# iot_env_mote.net
KiCad netlist of a schematic drawn in EAGLE
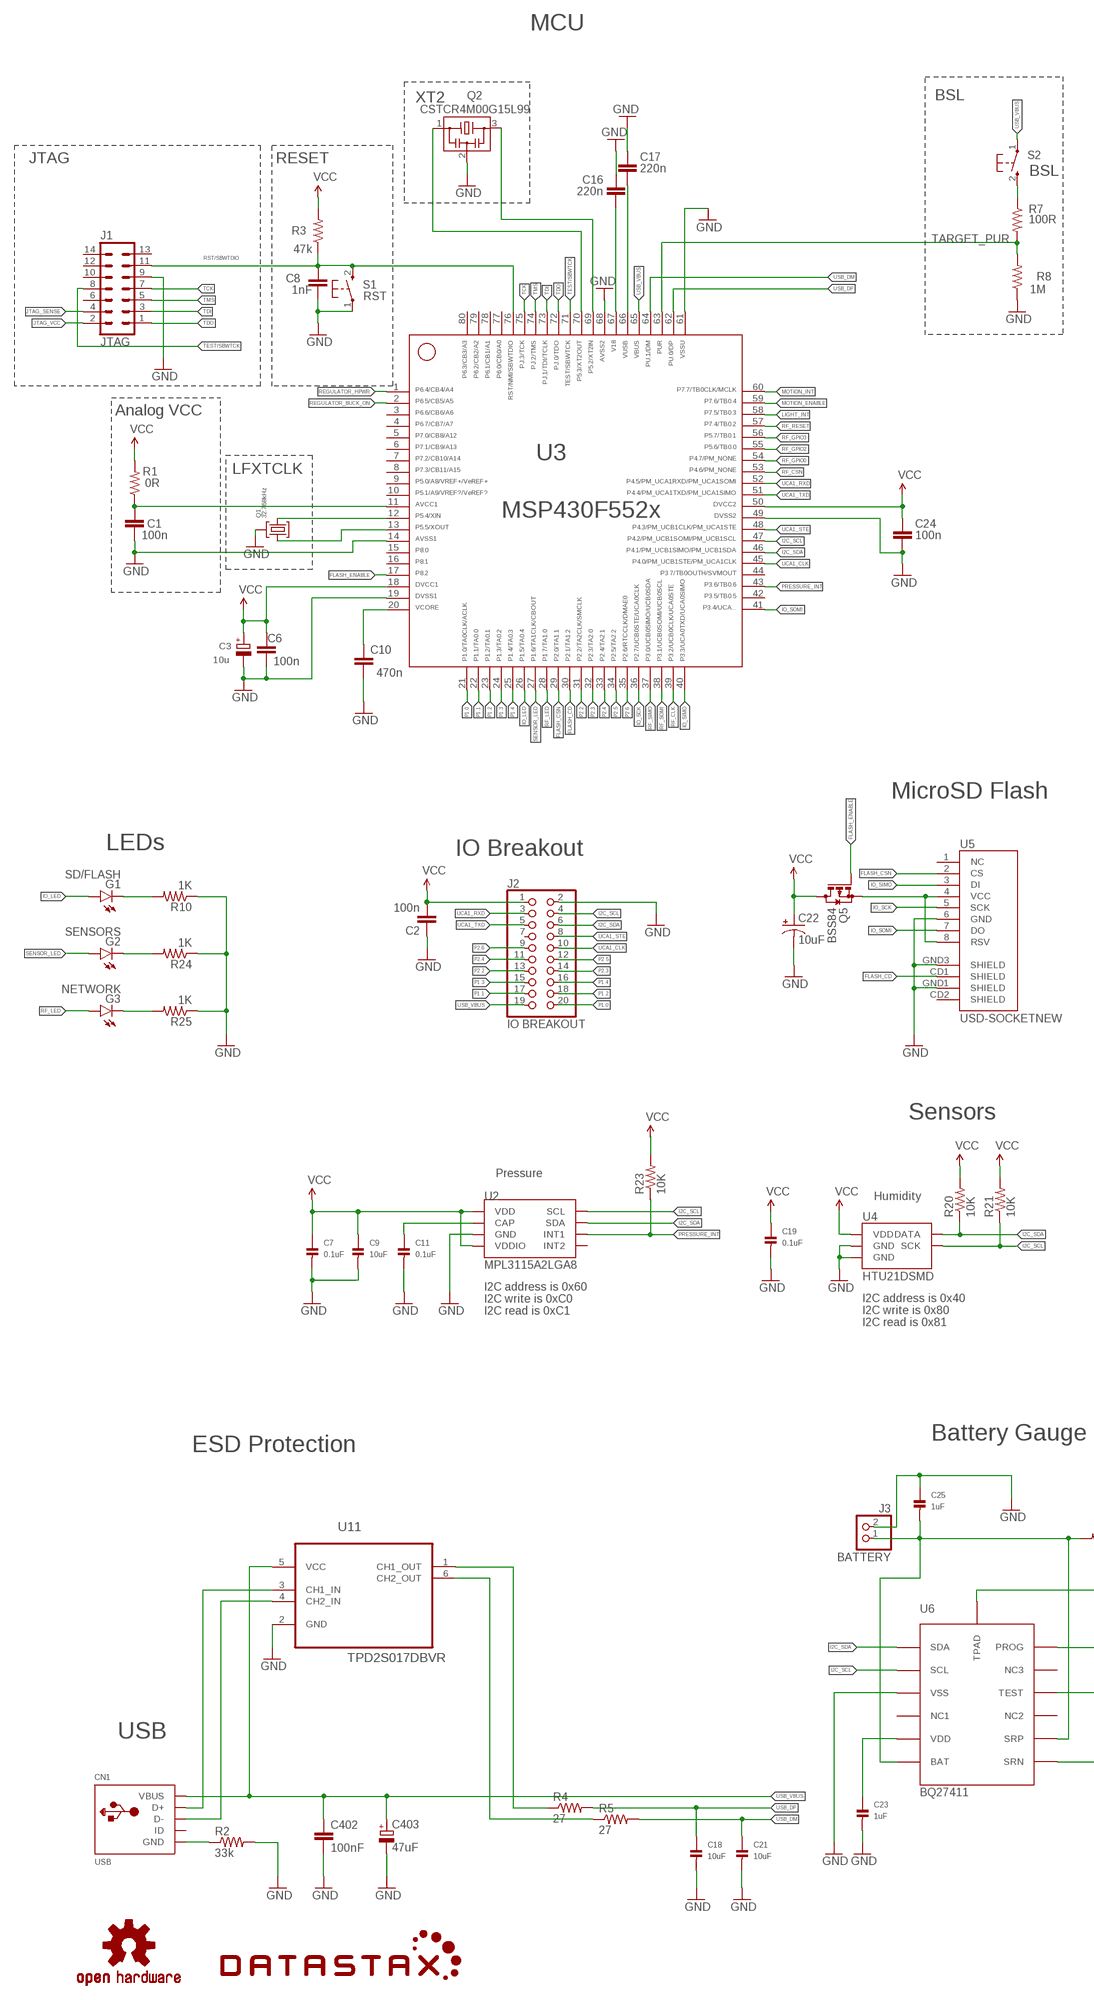
[diagram p0: schematic, sheet 1, part 1 of 2]
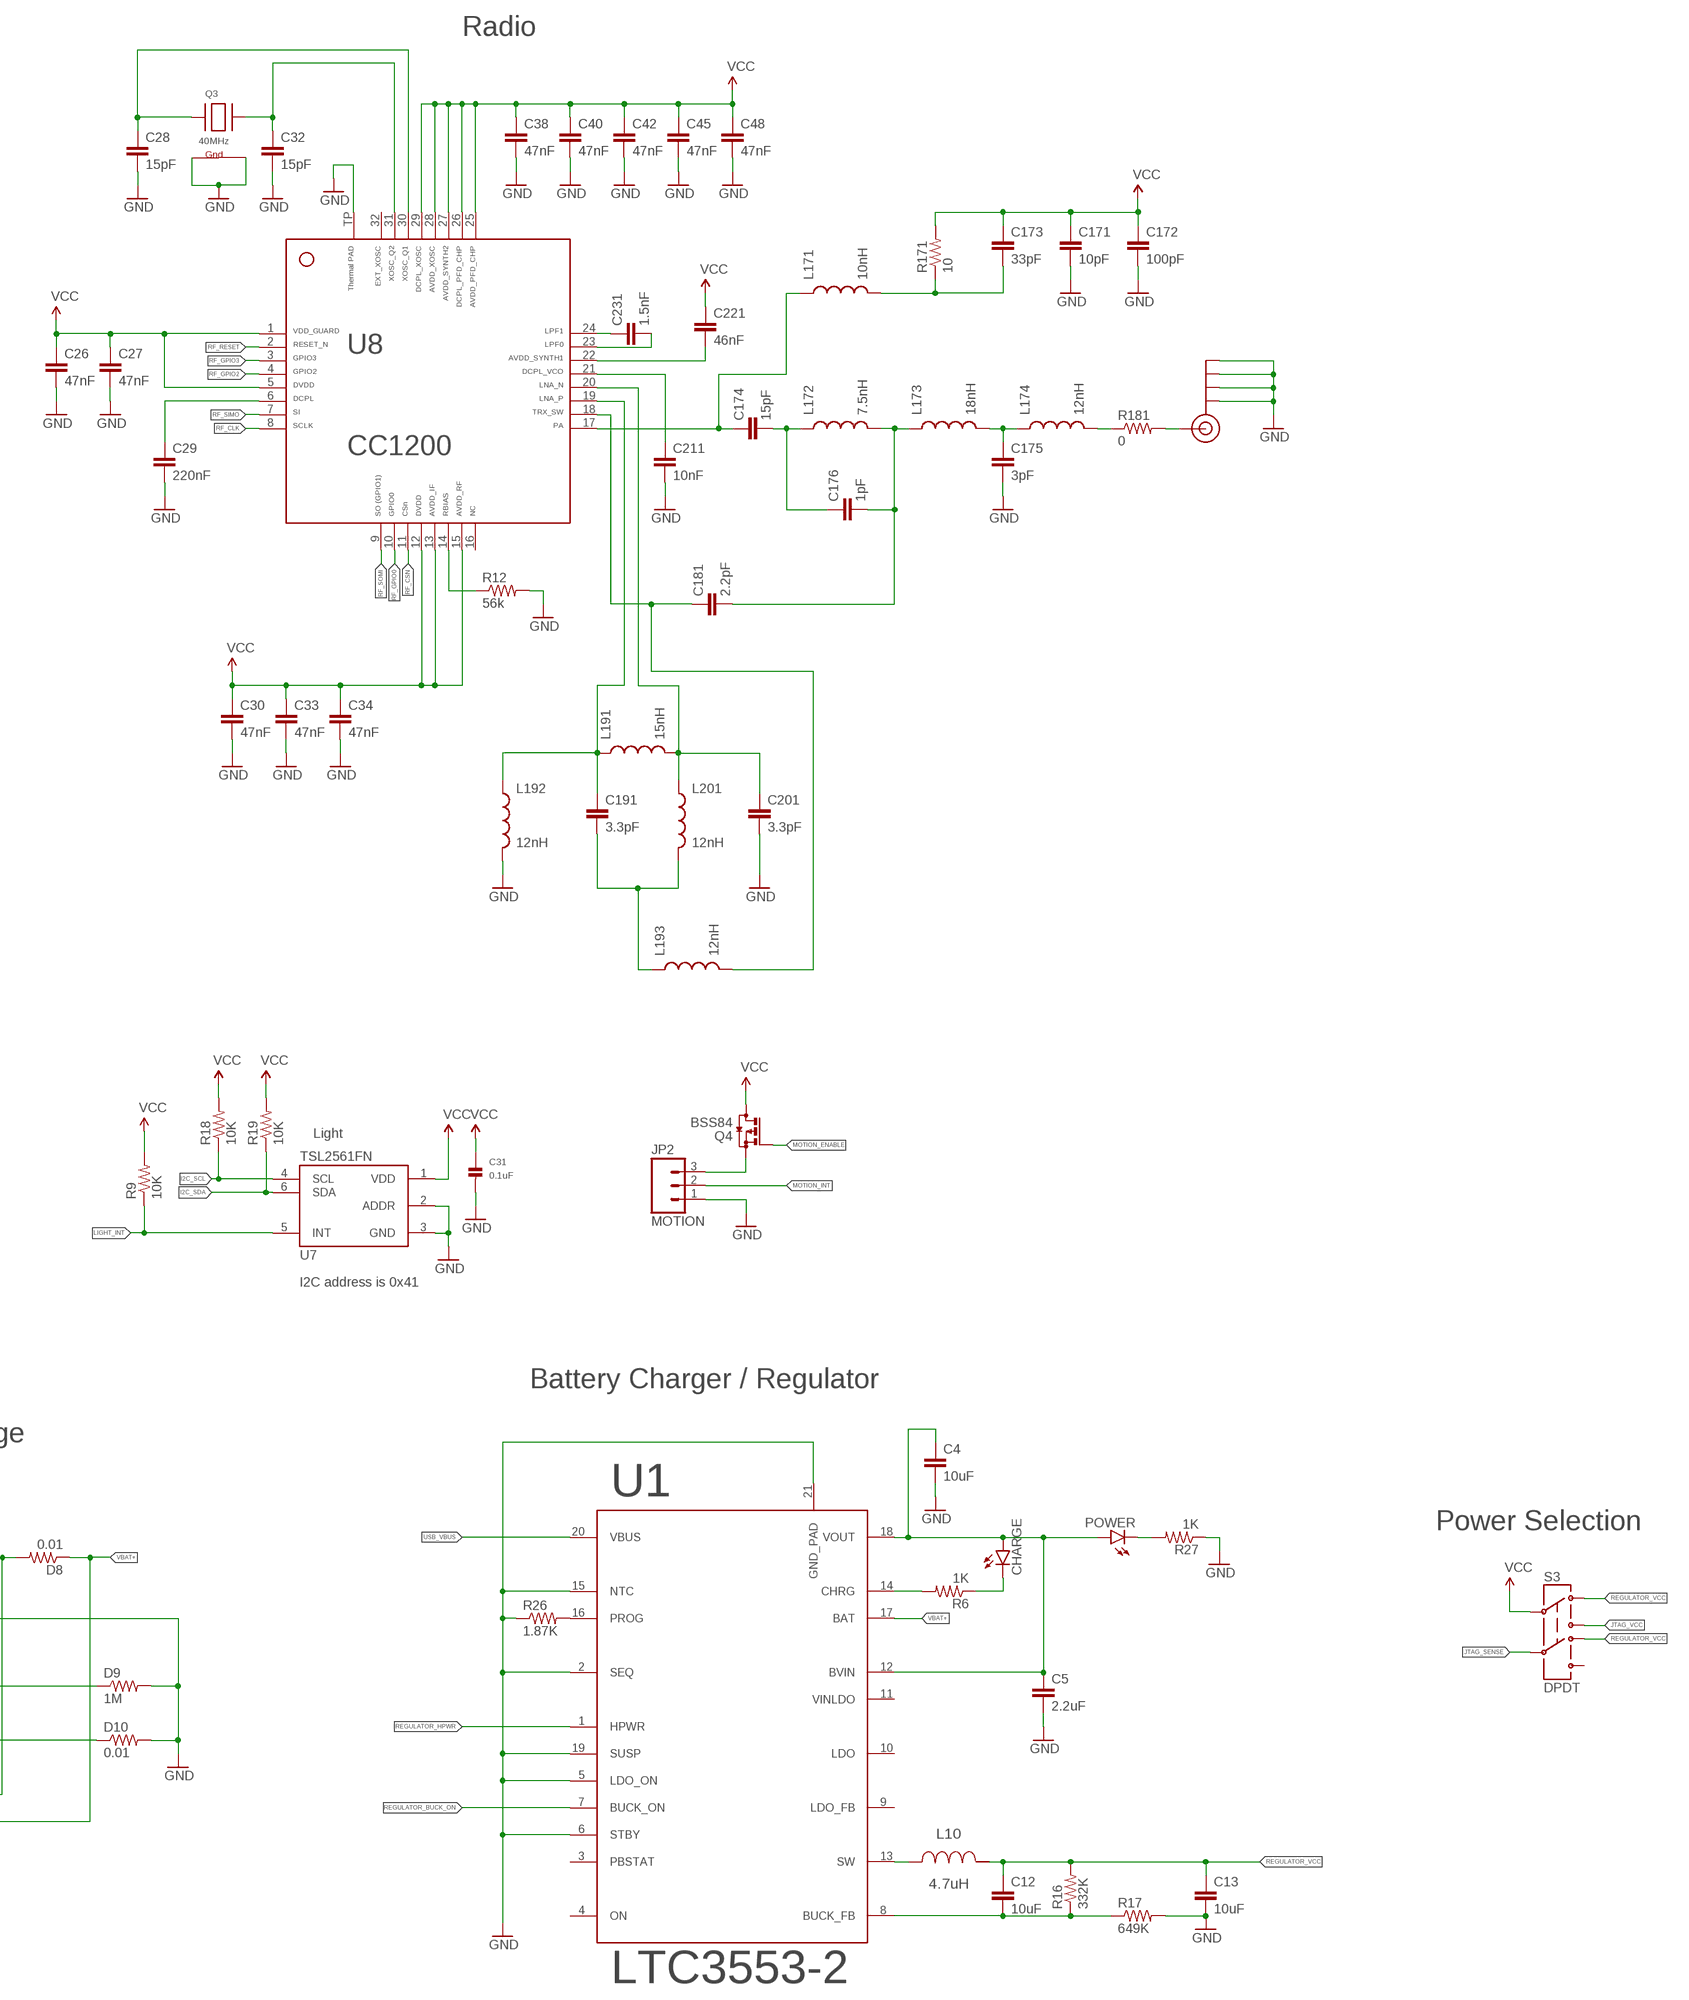
[diagram p1: schematic, sheet 1, part 2 of 2]

(export (version "E")
  (design (tool "Eeschema 10.0.6"))
  (components
    (comp (ref "C1")
      (value "100n")
      (footprint "eagle-import:C0402")
      (libsource (lib "eagle-import") (part "C-EUC0402"))
    )
    (comp (ref "C2")
      (value "100n")
      (footprint "eagle-import:C0402")
      (libsource (lib "eagle-import") (part "C-EUC0402"))
    )
    (comp (ref "C3")
      (value "10u")
      (footprint "eagle-import:A_3216-18R")
      (libsource (lib "eagle-import") (part "CPOL-EUA/3216-18R"))
    )
    (comp (ref "C4")
      (value "10uF")
      (footprint "eagle-import:0805")
      (fields (field (name "MPN") "06035A100FAT2A"))
      (libsource (lib "eagle-import") (part "CAP0805"))
    )
    (comp (ref "C5")
      (value "2.2uF")
      (footprint "eagle-import:0805")
      (fields (field (name "MPN") "06035A100FAT2A"))
      (libsource (lib "eagle-import") (part "CAP0805"))
    )
    (comp (ref "C6")
      (value "100n")
      (footprint "eagle-import:C0402")
      (libsource (lib "eagle-import") (part "C-EUC0402"))
    )
    (comp (ref "C7")
      (value "0.1uF")
      (footprint "eagle-import:0603")
      (fields (field (name "MPN") "0603YC104JAT2A"))
      (libsource (lib "eagle-import") (part "CAP_CERAMIC0603"))
    )
    (comp (ref "C8")
      (value "1nF")
      (footprint "eagle-import:C0402")
      (libsource (lib "eagle-import") (part "C-EUC0402"))
    )
    (comp (ref "C9")
      (value "10uF")
      (footprint "eagle-import:0603")
      (fields (field (name "MPN") "06035A100FAT2A"))
      (libsource (lib "eagle-import") (part "CAP_CERAMIC0603"))
    )
    (comp (ref "C10")
      (value "470n")
      (footprint "eagle-import:C0402")
      (libsource (lib "eagle-import") (part "C-EUC0402"))
    )
    (comp (ref "C11")
      (value "0.1uF")
      (footprint "eagle-import:0603")
      (fields (field (name "MPN") "0603YC104JAT2A"))
      (libsource (lib "eagle-import") (part "CAP_CERAMIC0603"))
    )
    (comp (ref "C12")
      (value "10uF")
      (footprint "eagle-import:0805")
      (fields (field (name "MPN") "06035A100FAT2A"))
      (libsource (lib "eagle-import") (part "CAP0805"))
    )
    (comp (ref "C13")
      (value "10uF")
      (footprint "eagle-import:0805")
      (fields (field (name "MPN") "06035A100FAT2A"))
      (libsource (lib "eagle-import") (part "CAP0805"))
    )
    (comp (ref "C16")
      (value "220n")
      (footprint "eagle-import:C0402")
      (libsource (lib "eagle-import") (part "C-EUC0402"))
    )
    (comp (ref "C17")
      (value "220n")
      (footprint "eagle-import:C0402")
      (libsource (lib "eagle-import") (part "C-EUC0402"))
    )
    (comp (ref "C18")
      (value "10uF")
      (footprint "eagle-import:0603")
      (fields (field (name "MPN") "06035A100FAT2A"))
      (libsource (lib "eagle-import") (part "CAP_CERAMIC0603"))
    )
    (comp (ref "C19")
      (value "0.1uF")
      (footprint "eagle-import:0603")
      (fields (field (name "MPN") "0603YC104JAT2A"))
      (libsource (lib "eagle-import") (part "CAP_CERAMIC0603"))
    )
    (comp (ref "C21")
      (value "10uF")
      (footprint "eagle-import:0603")
      (fields (field (name "MPN") "06035A100FAT2A"))
      (libsource (lib "eagle-import") (part "CAP_CERAMIC0603"))
    )
    (comp (ref "C22")
      (value "10uF")
      (footprint "eagle-import:A_3216-18R")
      (libsource (lib "eagle-import") (part "CPOL-USA/3216-18R"))
    )
    (comp (ref "C23")
      (value "1uF")
      (footprint "eagle-import:0603")
      (fields (field (name "MPN") "06035A100FAT2A"))
      (libsource (lib "eagle-import") (part "CAP_CERAMIC0603"))
    )
    (comp (ref "C24")
      (value "100n")
      (footprint "eagle-import:C0402")
      (libsource (lib "eagle-import") (part "C-EUC0402"))
    )
    (comp (ref "C25")
      (value "1uF")
      (footprint "eagle-import:0603")
      (fields (field (name "MPN") "06035A100FAT2A"))
      (libsource (lib "eagle-import") (part "CAP_CERAMIC0603"))
    )
    (comp (ref "C26")
      (value "47nF")
      (footprint "eagle-import:0402-CAP")
      (fields (field (name "MPN") "0603YC104JAT2A"))
      (libsource (lib "eagle-import") (part "CAP0402-CAP"))
    )
    (comp (ref "C27")
      (value "47nF")
      (footprint "eagle-import:0402-CAP")
      (fields (field (name "MPN") "0603YC104JAT2A"))
      (libsource (lib "eagle-import") (part "CAP0402-CAP"))
    )
    (comp (ref "C28")
      (value "15pF")
      (footprint "eagle-import:0402-CAP")
      (fields (field (name "MPN") "0603YC104JAT2A"))
      (libsource (lib "eagle-import") (part "CAP0402-CAP"))
    )
    (comp (ref "C29")
      (value "220nF")
      (footprint "eagle-import:0402-CAP")
      (fields (field (name "MPN") "0603YC104JAT2A"))
      (libsource (lib "eagle-import") (part "CAP0402-CAP"))
    )
    (comp (ref "C30")
      (value "47nF")
      (footprint "eagle-import:0402-CAP")
      (fields (field (name "MPN") "0603YC104JAT2A"))
      (libsource (lib "eagle-import") (part "CAP0402-CAP"))
    )
    (comp (ref "C31")
      (value "0.1uF")
      (footprint "eagle-import:0603")
      (fields (field (name "MPN") "0603YC104JAT2A"))
      (libsource (lib "eagle-import") (part "CAP_CERAMIC0603"))
    )
    (comp (ref "C32")
      (value "15pF")
      (footprint "eagle-import:0402-CAP")
      (fields (field (name "MPN") "0603YC104JAT2A"))
      (libsource (lib "eagle-import") (part "CAP0402-CAP"))
    )
    (comp (ref "C33")
      (value "47nF")
      (footprint "eagle-import:0402-CAP")
      (fields (field (name "MPN") "0603YC104JAT2A"))
      (libsource (lib "eagle-import") (part "CAP0402-CAP"))
    )
    (comp (ref "C34")
      (value "47nF")
      (footprint "eagle-import:0402-CAP")
      (fields (field (name "MPN") "0603YC104JAT2A"))
      (libsource (lib "eagle-import") (part "CAP0402-CAP"))
    )
    (comp (ref "C38")
      (value "47nF")
      (footprint "eagle-import:0402-CAP")
      (fields (field (name "MPN") "0603YC104JAT2A"))
      (libsource (lib "eagle-import") (part "CAP0402-CAP"))
    )
    (comp (ref "C40")
      (value "47nF")
      (footprint "eagle-import:0402-CAP")
      (fields (field (name "MPN") "0603YC104JAT2A"))
      (libsource (lib "eagle-import") (part "CAP0402-CAP"))
    )
    (comp (ref "C42")
      (value "47nF")
      (footprint "eagle-import:0402-CAP")
      (fields (field (name "MPN") "0603YC104JAT2A"))
      (libsource (lib "eagle-import") (part "CAP0402-CAP"))
    )
    (comp (ref "C45")
      (value "47nF")
      (footprint "eagle-import:0402-CAP")
      (fields (field (name "MPN") "0603YC104JAT2A"))
      (libsource (lib "eagle-import") (part "CAP0402-CAP"))
    )
    (comp (ref "C48")
      (value "47nF")
      (footprint "eagle-import:0402-CAP")
      (fields (field (name "MPN") "0603YC104JAT2A"))
      (libsource (lib "eagle-import") (part "CAP0402-CAP"))
    )
    (comp (ref "C171")
      (value "10pF")
      (footprint "eagle-import:0402-CAP")
      (fields (field (name "MPN") "0603YC104JAT2A"))
      (libsource (lib "eagle-import") (part "CAP0402-CAP"))
    )
    (comp (ref "C172")
      (value "100pF")
      (footprint "eagle-import:0402-CAP")
      (fields (field (name "MPN") "0603YC104JAT2A"))
      (libsource (lib "eagle-import") (part "CAP0402-CAP"))
    )
    (comp (ref "C173")
      (value "33pF")
      (footprint "eagle-import:0402-CAP")
      (fields (field (name "MPN") "0603YC104JAT2A"))
      (libsource (lib "eagle-import") (part "CAP0402-CAP"))
    )
    (comp (ref "C174")
      (value "15pF")
      (footprint "eagle-import:0402-CAP")
      (fields (field (name "MPN") "0603YC104JAT2A"))
      (libsource (lib "eagle-import") (part "CAP0402-CAP"))
    )
    (comp (ref "C175")
      (value "3pF")
      (footprint "eagle-import:0402-CAP")
      (fields (field (name "MPN") "0603YC104JAT2A"))
      (libsource (lib "eagle-import") (part "CAP0402-CAP"))
    )
    (comp (ref "C176")
      (value "1pF")
      (footprint "eagle-import:0402-CAP")
      (fields (field (name "MPN") "0603YC104JAT2A"))
      (libsource (lib "eagle-import") (part "CAP0402-CAP"))
    )
    (comp (ref "C181")
      (value "2.2pF")
      (footprint "eagle-import:0402-CAP")
      (fields (field (name "MPN") "0603YC104JAT2A"))
      (libsource (lib "eagle-import") (part "CAP0402-CAP"))
    )
    (comp (ref "C191")
      (value "3.3pF")
      (footprint "eagle-import:0402-CAP")
      (fields (field (name "MPN") "0603YC104JAT2A"))
      (libsource (lib "eagle-import") (part "CAP0402-CAP"))
    )
    (comp (ref "C201")
      (value "3.3pF")
      (footprint "eagle-import:0402-CAP")
      (fields (field (name "MPN") "0603YC104JAT2A"))
      (libsource (lib "eagle-import") (part "CAP0402-CAP"))
    )
    (comp (ref "C211")
      (value "10nF")
      (footprint "eagle-import:0402-CAP")
      (fields (field (name "MPN") "0603YC104JAT2A"))
      (libsource (lib "eagle-import") (part "CAP0402-CAP"))
    )
    (comp (ref "C221")
      (value "46nF")
      (footprint "eagle-import:0402-CAP")
      (fields (field (name "MPN") "0603YC104JAT2A"))
      (libsource (lib "eagle-import") (part "CAP0402-CAP"))
    )
    (comp (ref "C231")
      (value "1.5nF")
      (footprint "eagle-import:0402-CAP")
      (fields (field (name "MPN") "0603YC104JAT2A"))
      (libsource (lib "eagle-import") (part "CAP0402-CAP"))
    )
    (comp (ref "C402")
      (value "100nF")
      (footprint "eagle-import:C0402")
      (libsource (lib "eagle-import") (part "C-EUC0402"))
    )
    (comp (ref "C403")
      (value "47uF")
      (footprint "eagle-import:A_3216-18R")
      (libsource (lib "eagle-import") (part "CPOL-EUA/3216-18R"))
    )
    (comp (ref "CHARGE")
      (value "LED0603")
      (footprint "eagle-import:LED-0603")
      (libsource (lib "eagle-import") (part "LED0603"))
    )
    (comp (ref "CN1")
      (value "USB")
      (footprint "eagle-import:USB-MINIB")
      (libsource (lib "eagle-import") (part "USBMINIB"))
    )
    (comp (ref "D8")
      (value "0.01")
      (footprint "eagle-import:R0402")
      (libsource (lib "eagle-import") (part "R-US_R0402"))
    )
    (comp (ref "D9")
      (value "1M")
      (footprint "eagle-import:R0402")
      (libsource (lib "eagle-import") (part "R-US_R0402"))
    )
    (comp (ref "D10")
      (value "0.01")
      (footprint "eagle-import:R0402")
      (libsource (lib "eagle-import") (part "R-US_R0402"))
    )
    (comp (ref "G1")
      (value "SD/FLASH")
      (footprint "eagle-import:LED-0603")
      (libsource (lib "eagle-import") (part "LED0603"))
    )
    (comp (ref "G2")
      (value "SENSORS")
      (footprint "eagle-import:LED-0603")
      (libsource (lib "eagle-import") (part "LED0603"))
    )
    (comp (ref "G3")
      (value "NETWORK")
      (footprint "eagle-import:LED-0603")
      (libsource (lib "eagle-import") (part "LED0603"))
    )
    (comp (ref "J1")
      (value "JTAG")
      (footprint "eagle-import:ML14")
      (libsource (lib "eagle-import") (part "ML14"))
    )
    (comp (ref "J2")
      (value "IO BREAKOUT")
      (footprint "eagle-import:2X10")
      (libsource (lib "eagle-import") (part "PINHD-2X10"))
    )
    (comp (ref "J3")
      (value "BATTERY")
      (footprint "eagle-import:JST-PH-2-SMT-RA")
      (libsource (lib "eagle-import") (part "JST_2PIN-SMT-RA"))
    )
    (comp (ref "JP2")
      (value "MOTION")
      (footprint "eagle-import:JST-3-PTH-VERT")
      (libsource (lib "eagle-import") (part "M03JST-PTH-VERT"))
    )
    (comp (ref "L10")
      (value "4.7uH")
      (footprint "eagle-import:SDR0403")
      (fields (field (name "MANUFACTURER_PART_NUMBER") "SDR0403-2R2ML"))
      (libsource (lib "eagle-import") (part "SDR0403-2R2MLSDR0403-2R2ML"))
    )
    (comp (ref "L171")
      (value "10nH")
      (footprint "eagle-import:C0402")
      (libsource (lib "eagle-import") (part "INDUCTOR0402"))
    )
    (comp (ref "L172")
      (value "7.5nH")
      (footprint "eagle-import:C0402")
      (libsource (lib "eagle-import") (part "INDUCTOR0402"))
    )
    (comp (ref "L173")
      (value "18nH")
      (footprint "eagle-import:C0402")
      (libsource (lib "eagle-import") (part "INDUCTOR0402"))
    )
    (comp (ref "L174")
      (value "12nH")
      (footprint "eagle-import:C0402")
      (libsource (lib "eagle-import") (part "INDUCTOR0402"))
    )
    (comp (ref "L191")
      (value "15nH")
      (footprint "eagle-import:C0402")
      (libsource (lib "eagle-import") (part "INDUCTOR0402"))
    )
    (comp (ref "L192")
      (value "12nH")
      (footprint "eagle-import:C0402")
      (libsource (lib "eagle-import") (part "INDUCTOR0402"))
    )
    (comp (ref "L193")
      (value "12nH")
      (footprint "eagle-import:C0402")
      (libsource (lib "eagle-import") (part "INDUCTOR0402"))
    )
    (comp (ref "L201")
      (value "12nH")
      (footprint "eagle-import:C0402")
      (libsource (lib "eagle-import") (part "INDUCTOR0402"))
    )
    (comp (ref "LOGO1")
      (value "OSHW-LOGOL")
      (footprint "eagle-import:OSHW-LOGO-L")
      (libsource (lib "eagle-import") (part "OSHW-LOGOL"))
    )
    (comp (ref "POWER")
      (value "LED0603")
      (footprint "eagle-import:LED-0603")
      (libsource (lib "eagle-import") (part "LED0603"))
    )
    (comp (ref "Q1")
      (value "32.768kHz")
      (footprint "eagle-import:MS3V-T1R")
      (libsource (lib "eagle-import") (part "MS3V-T1R"))
    )
    (comp (ref "Q2")
      (value "CSTCR4M00G15L99")
      (footprint "eagle-import:MURATA-FILTER_CSTCR")
      (fields (field (name "MPN") "CSTCR6M00G53-R0"))
      (libsource (lib "eagle-import") (part "MURATA-FILTER_CSTCR6M00G53Z"))
    )
    (comp (ref "Q3")
      (value "40MHz")
      (footprint "eagle-import:NX3225")
      (libsource (lib "eagle-import") (part "XTAL-4-3225"))
    )
    (comp (ref "Q4")
      (value "BSS84")
      (footprint "eagle-import:SOT23")
      (libsource (lib "eagle-import") (part "BSS84"))
    )
    (comp (ref "Q5")
      (value "BSS84")
      (footprint "eagle-import:SOT23")
      (libsource (lib "eagle-import") (part "BSS84"))
    )
    (comp (ref "R1")
      (value "0R")
      (footprint "eagle-import:R0402")
      (libsource (lib "eagle-import") (part "R-US_R0402"))
    )
    (comp (ref "R2")
      (value "33k")
      (footprint "eagle-import:0402-RES")
      (libsource (lib "eagle-import") (part "RESISTOR0402-RES"))
    )
    (comp (ref "R3")
      (value "47k")
      (footprint "eagle-import:R0402")
      (libsource (lib "eagle-import") (part "R-US_R0402"))
    )
    (comp (ref "R4")
      (value "27")
      (footprint "eagle-import:0402-RES")
      (libsource (lib "eagle-import") (part "RESISTOR0402-RES"))
    )
    (comp (ref "R5")
      (value "27")
      (footprint "eagle-import:0402-RES")
      (libsource (lib "eagle-import") (part "RESISTOR0402-RES"))
    )
    (comp (ref "R6")
      (value "1K")
      (footprint "eagle-import:R0402")
      (libsource (lib "eagle-import") (part "R-US_R0402"))
    )
    (comp (ref "R7")
      (value "100R")
      (footprint "eagle-import:R0402")
      (libsource (lib "eagle-import") (part "R-US_R0402"))
    )
    (comp (ref "R8")
      (value "1M")
      (footprint "eagle-import:R0402")
      (libsource (lib "eagle-import") (part "R-US_R0402"))
    )
    (comp (ref "R9")
      (value "10K")
      (footprint "eagle-import:R0402")
      (fields (field (name "MPN") "ERJ-P03F1002V"))
      (libsource (lib "eagle-import") (part "R-US_R0402"))
    )
    (comp (ref "R10")
      (value "1K")
      (footprint "eagle-import:0402-RES")
      (libsource (lib "eagle-import") (part "RESISTOR0402-RES"))
    )
    (comp (ref "R12")
      (value "56k")
      (footprint "eagle-import:0402-RES")
      (libsource (lib "eagle-import") (part "RESISTOR0402-RES"))
    )
    (comp (ref "R16")
      (value "332K")
      (footprint "eagle-import:R0402")
      (libsource (lib "eagle-import") (part "R-US_R0402"))
    )
    (comp (ref "R17")
      (value "649K")
      (footprint "eagle-import:R0402")
      (libsource (lib "eagle-import") (part "R-US_R0402"))
    )
    (comp (ref "R18")
      (value "10K")
      (footprint "eagle-import:R0402")
      (fields (field (name "MPN") "ERJ-P03F1002V"))
      (libsource (lib "eagle-import") (part "R-US_R0402"))
    )
    (comp (ref "R19")
      (value "10K")
      (footprint "eagle-import:R0402")
      (fields (field (name "MPN") "ERJ-P03F1002V"))
      (libsource (lib "eagle-import") (part "R-US_R0402"))
    )
    (comp (ref "R20")
      (value "10K")
      (footprint "eagle-import:R0402")
      (fields (field (name "MPN") "ERJ-P03F1002V"))
      (libsource (lib "eagle-import") (part "R-US_R0402"))
    )
    (comp (ref "R21")
      (value "10K")
      (footprint "eagle-import:R0402")
      (fields (field (name "MPN") "ERJ-P03F1002V"))
      (libsource (lib "eagle-import") (part "R-US_R0402"))
    )
    (comp (ref "R23")
      (value "10K")
      (footprint "eagle-import:R0402")
      (fields (field (name "MPN") "ERJ-P03F1002V"))
      (libsource (lib "eagle-import") (part "R-US_R0402"))
    )
    (comp (ref "R24")
      (value "1K")
      (footprint "eagle-import:0402-RES")
      (libsource (lib "eagle-import") (part "RESISTOR0402-RES"))
    )
    (comp (ref "R25")
      (value "1K")
      (footprint "eagle-import:0402-RES")
      (libsource (lib "eagle-import") (part "RESISTOR0402-RES"))
    )
    (comp (ref "R26")
      (value "1.87K")
      (footprint "eagle-import:R0402")
      (libsource (lib "eagle-import") (part "R-US_R0402"))
    )
    (comp (ref "R27")
      (value "1K")
      (footprint "eagle-import:R0402")
      (libsource (lib "eagle-import") (part "R-US_R0402"))
    )
    (comp (ref "R171")
      (value "10")
      (footprint "eagle-import:0402-RES")
      (libsource (lib "eagle-import") (part "RESISTOR0402-RES"))
    )
    (comp (ref "R181")
      (value "0")
      (footprint "eagle-import:0402-RES")
      (libsource (lib "eagle-import") (part "RESISTOR0402-RES"))
    )
    (comp (ref "S1")
      (value "RST")
      (footprint "eagle-import:PBTH")
      (libsource (lib "eagle-import") (part "PB"))
    )
    (comp (ref "S2")
      (value "BSL")
      (footprint "eagle-import:PBTH")
      (libsource (lib "eagle-import") (part "PB"))
    )
    (comp (ref "S3")
      (value "DPDT")
      (footprint "eagle-import:AYZ0202")
      (libsource (lib "eagle-import") (part "SWITCH-DPDTAYZ0202"))
    )
    (comp (ref "SMA")
      (value "SMA_EDGE")
      (footprint "eagle-import:SMA-EDGE")
      (libsource (lib "eagle-import") (part "SMA_EDGE"))
    )
    (comp (ref "U$1")
      (value "DATASTAX_LOGO")
      (footprint "eagle-import:DATASTAX_LOGO")
      (libsource (lib "eagle-import") (part "DATASTAX_LOGO"))
    )
    (comp (ref "U1")
      (value "LTC3553-2")
      (footprint "eagle-import:QFN-20-0.4MM")
      (libsource (lib "eagle-import") (part "LTC3553-2"))
    )
    (comp (ref "U2")
      (value "MPL3115A2LGA8")
      (footprint "eagle-import:LGA8")
      (fields (field (name "MPN") "MPL3115A2"))
      (libsource (lib "eagle-import") (part "MPL3115A2LGA8"))
    )
    (comp (ref "U3")
      (value "MSP430F5529IPNR")
      (footprint "eagle-import:PN80")
      (libsource (lib "eagle-import") (part "F552X---PN80"))
    )
    (comp (ref "U4")
      (value "HTU21DSMD")
      (footprint "eagle-import:HTU21D")
      (fields (field (name "MPN") "HTU21D"))
      (libsource (lib "eagle-import") (part "HTU21DSMD"))
    )
    (comp (ref "U5")
      (value "USD-SOCKETNEW")
      (footprint "eagle-import:MICRO-SD-SOCKET-PP")
      (libsource (lib "eagle-import") (part "USD-SOCKETNEW"))
    )
    (comp (ref "U6")
      (value "BQ27411")
      (footprint "eagle-import:VSON40P400X400X12")
      (libsource (lib "eagle-import") (part "BQ27411"))
    )
    (comp (ref "U7")
      (value "TSL2561FN")
      (footprint "eagle-import:FN-6")
      (fields (field (name "MPN") "TSL2561T"))
      (libsource (lib "eagle-import") (part "TSL2561FN"))
    )
    (comp (ref "U8")
      (value "CC1200")
      (footprint "eagle-import:RHB32")
      (libsource (lib "eagle-import") (part "CC1200"))
    )
    (comp (ref "U11")
      (value "TPD2S017DBVR")
      (footprint "eagle-import:SOT95P280X145-6N")
      (libsource (lib "eagle-import") (part "TPD2S017DBVR"))
    )
  )
  (nets
    (net (code "1") (name "FLASH_CD") (class "Default")
      (node (ref "U3") (pin "30") (pinfunction "30_30") (pintype "bidirectional"))
      (node (ref "U5") (pin "CD1") (pinfunction "SHIELD_CD1") (pintype "bidirectional"))
    )
    (net (code "2") (name "FLASH_CSN") (class "Default")
      (node (ref "U3") (pin "29") (pinfunction "29_29") (pintype "bidirectional"))
      (node (ref "U5") (pin "2") (pinfunction "CS_2") (pintype "bidirectional"))
    )
    (net (code "3") (name "FLASH_ENABLE") (class "Default")
      (node (ref "Q5") (pin "1") (pinfunction "G_1") (pintype "passive"))
      (node (ref "U3") (pin "17") (pinfunction "17_17") (pintype "bidirectional"))
    )
    (net (code "4") (name "GND") (class "Default")
      (node (ref "C1") (pin "2") (pinfunction "2_2") (pintype "passive"))
      (node (ref "C10") (pin "1") (pinfunction "1_1") (pintype "passive"))
      (node (ref "C11") (pin "2") (pinfunction "P$2_2") (pintype "passive"))
      (node (ref "C13") (pin "2") (pinfunction "2_2") (pintype "passive"))
      (node (ref "C16") (pin "2") (pinfunction "2_2") (pintype "passive"))
      (node (ref "C17") (pin "2") (pinfunction "2_2") (pintype "passive"))
      (node (ref "C171") (pin "2") (pinfunction "2_2") (pintype "passive"))
      (node (ref "C172") (pin "2") (pinfunction "2_2") (pintype "passive"))
      (node (ref "C175") (pin "2") (pinfunction "2_2") (pintype "passive"))
      (node (ref "C18") (pin "2") (pinfunction "P$2_2") (pintype "passive"))
      (node (ref "C19") (pin "2") (pinfunction "P$2_2") (pintype "passive"))
      (node (ref "C2") (pin "1") (pinfunction "1_1") (pintype "passive"))
      (node (ref "C201") (pin "2") (pinfunction "2_2") (pintype "passive"))
      (node (ref "C21") (pin "2") (pinfunction "P$2_2") (pintype "passive"))
      (node (ref "C211") (pin "2") (pinfunction "2_2") (pintype "passive"))
      (node (ref "C22") (pin "-") (pinfunction "-_-") (pintype "passive"))
      (node (ref "C23") (pin "2") (pinfunction "P$2_2") (pintype "passive"))
      (node (ref "C24") (pin "2") (pinfunction "2_2") (pintype "passive"))
      (node (ref "C25") (pin "1") (pinfunction "P$1_1") (pintype "passive"))
      (node (ref "C26") (pin "2") (pinfunction "2_2") (pintype "passive"))
      (node (ref "C27") (pin "2") (pinfunction "2_2") (pintype "passive"))
      (node (ref "C28") (pin "2") (pinfunction "2_2") (pintype "passive"))
      (node (ref "C29") (pin "2") (pinfunction "2_2") (pintype "passive"))
      (node (ref "C3") (pin "-") (pinfunction "-_-") (pintype "passive"))
      (node (ref "C30") (pin "2") (pinfunction "2_2") (pintype "passive"))
      (node (ref "C31") (pin "2") (pinfunction "P$2_2") (pintype "passive"))
      (node (ref "C32") (pin "2") (pinfunction "2_2") (pintype "passive"))
      (node (ref "C33") (pin "2") (pinfunction "2_2") (pintype "passive"))
      (node (ref "C34") (pin "2") (pinfunction "2_2") (pintype "passive"))
      (node (ref "C38") (pin "2") (pinfunction "2_2") (pintype "passive"))
      (node (ref "C4") (pin "2") (pinfunction "2_2") (pintype "passive"))
      (node (ref "C40") (pin "2") (pinfunction "2_2") (pintype "passive"))
      (node (ref "C402") (pin "2") (pinfunction "2_2") (pintype "passive"))
      (node (ref "C403") (pin "-") (pinfunction "-_-") (pintype "passive"))
      (node (ref "C42") (pin "2") (pinfunction "2_2") (pintype "passive"))
      (node (ref "C45") (pin "2") (pinfunction "2_2") (pintype "passive"))
      (node (ref "C48") (pin "2") (pinfunction "2_2") (pintype "passive"))
      (node (ref "C5") (pin "2") (pinfunction "2_2") (pintype "passive"))
      (node (ref "C6") (pin "1") (pinfunction "1_1") (pintype "passive"))
      (node (ref "C7") (pin "2") (pinfunction "P$2_2") (pintype "passive"))
      (node (ref "C8") (pin "2") (pinfunction "2_2") (pintype "passive"))
      (node (ref "C9") (pin "2") (pinfunction "P$2_2") (pintype "passive"))
      (node (ref "D10") (pin "2") (pinfunction "2_2") (pintype "passive"))
      (node (ref "D9") (pin "2") (pinfunction "2_2") (pintype "passive"))
      (node (ref "J1") (pin "9") (pinfunction "9_9") (pintype "passive"))
      (node (ref "J2") (pin "2") (pinfunction "2_2") (pintype "passive"))
      (node (ref "J3") (pin "2") (pinfunction "1_2") (pintype "passive"))
      (node (ref "JP2") (pin "1") (pinfunction "1_1") (pintype "passive"))
      (node (ref "L192") (pin "2") (pinfunction "2_2") (pintype "passive"))
      (node (ref "Q1") (pin "P3") (pinfunction "GND_P3") (pintype "power_in"))
      (node (ref "Q2") (pin "2") (pinfunction "2_2") (pintype "passive"))
      (node (ref "Q3") (pin "2") (pinfunction "G2_2") (pintype "power_in"))
      (node (ref "Q3") (pin "4") (pinfunction "G1_4") (pintype "power_in"))
      (node (ref "R10") (pin "1") (pinfunction "1_1") (pintype "passive"))
      (node (ref "R12") (pin "2") (pinfunction "2_2") (pintype "passive"))
      (node (ref "R17") (pin "2") (pinfunction "2_2") (pintype "passive"))
      (node (ref "R2") (pin "2") (pinfunction "2_2") (pintype "passive"))
      (node (ref "R24") (pin "1") (pinfunction "1_1") (pintype "passive"))
      (node (ref "R25") (pin "1") (pinfunction "1_1") (pintype "passive"))
      (node (ref "R26") (pin "1") (pinfunction "1_1") (pintype "passive"))
      (node (ref "R27") (pin "1") (pinfunction "1_1") (pintype "passive"))
      (node (ref "R8") (pin "1") (pinfunction "1_1") (pintype "passive"))
      (node (ref "S1") (pin "1") (pinfunction "P_1") (pintype "passive"))
      (node (ref "SMA") (pin "GND@0") (pinfunction "GND_GND@0") (pintype "bidirectional"))
      (node (ref "SMA") (pin "GND@1") (pinfunction "GND_GND@1") (pintype "bidirectional"))
      (node (ref "SMA") (pin "GND@2") (pinfunction "GND_GND@2") (pintype "bidirectional"))
      (node (ref "SMA") (pin "GND@3") (pinfunction "GND_GND@3") (pintype "bidirectional"))
      (node (ref "U1") (pin "15") (pinfunction "NTC_15") (pintype "power_in"))
      (node (ref "U1") (pin "19") (pinfunction "SUSP_19") (pintype "input"))
      (node (ref "U1") (pin "2") (pinfunction "SEQ_2") (pintype "power_in"))
      (node (ref "U1") (pin "21") (pinfunction "GND_PAD_21") (pintype "power_in"))
      (node (ref "U1") (pin "5") (pinfunction "LDO_ON_5") (pintype "input"))
      (node (ref "U1") (pin "6") (pinfunction "STBY_6") (pintype "input"))
      (node (ref "U11") (pin "2") (pinfunction "GND_2") (pintype "passive"))
      (node (ref "U2") (pin "3") (pinfunction "GND_3") (pintype "power_in"))
      (node (ref "U3") (pin "14") (pinfunction "14_14") (pintype "power_in"))
      (node (ref "U3") (pin "19") (pinfunction "19_19") (pintype "power_in"))
      (node (ref "U3") (pin "49") (pinfunction "49_49") (pintype "power_in"))
      (node (ref "U3") (pin "61") (pinfunction "61_61") (pintype "power_in"))
      (node (ref "U3") (pin "68") (pinfunction "68_68") (pintype "power_in"))
      (node (ref "U4") (pin "7") (pinfunction "GND_7") (pintype "power_in"))
      (node (ref "U4") (pin "GND") (pinfunction "GND_GND") (pintype "power_in"))
      (node (ref "U5") (pin "6") (pinfunction "GND_6") (pintype "bidirectional"))
      (node (ref "U5") (pin "GND1") (pinfunction "SHIELD_GND1") (pintype "bidirectional"))
      (node (ref "U5") (pin "GND3") (pinfunction "SHIELD_GND3") (pintype "bidirectional"))
      (node (ref "U6") (pin "GND") (pinfunction "TPAD_GND") (pintype "bidirectional"))
      (node (ref "U6") (pin "VSS") (pinfunction "VSS_VSS") (pintype "bidirectional"))
      (node (ref "U7") (pin "2") (pinfunction "ADDR_2") (pintype "input"))
      (node (ref "U7") (pin "3") (pinfunction "GND_3") (pintype "power_in"))
      (node (ref "U8") (pin "TP") (pinfunction "33_TP") (pintype "power_in"))
    )
    (net (code "5") (name "I2C_SCL") (class "Default")
      (node (ref "J2") (pin "4") (pinfunction "4_4") (pintype "passive"))
      (node (ref "R18") (pin "1") (pinfunction "1_1") (pintype "passive"))
      (node (ref "R21") (pin "1") (pinfunction "1_1") (pintype "passive"))
      (node (ref "U2") (pin "8") (pinfunction "SCL_8") (pintype "bidirectional"))
      (node (ref "U3") (pin "47") (pinfunction "47_47") (pintype "bidirectional"))
      (node (ref "U4") (pin "SCK") (pinfunction "SCK_SCK") (pintype "input"))
      (node (ref "U6") (pin "SCL") (pinfunction "SCL_SCL") (pintype "bidirectional"))
      (node (ref "U7") (pin "4") (pinfunction "SCL_4") (pintype "input"))
    )
    (net (code "6") (name "I2C_SDA") (class "Default")
      (node (ref "J2") (pin "6") (pinfunction "6_6") (pintype "passive"))
      (node (ref "R19") (pin "1") (pinfunction "1_1") (pintype "passive"))
      (node (ref "R20") (pin "1") (pinfunction "1_1") (pintype "passive"))
      (node (ref "U2") (pin "7") (pinfunction "SDA_7") (pintype "bidirectional"))
      (node (ref "U3") (pin "46") (pinfunction "46_46") (pintype "bidirectional"))
      (node (ref "U4") (pin "DATA") (pinfunction "DATA_DATA") (pintype "bidirectional"))
      (node (ref "U6") (pin "SDA") (pinfunction "SDA_SDA") (pintype "bidirectional"))
      (node (ref "U7") (pin "6") (pinfunction "SDA_6") (pintype "bidirectional"))
    )
    (net (code "7") (name "IO_LED") (class "Default")
      (node (ref "G1") (pin "A") (pinfunction "A_A") (pintype "passive"))
      (node (ref "U3") (pin "26") (pinfunction "26_26") (pintype "bidirectional"))
    )
    (net (code "8") (name "IO_SCK") (class "Default")
      (node (ref "U3") (pin "36") (pinfunction "36_36") (pintype "bidirectional"))
      (node (ref "U5") (pin "5") (pinfunction "SCK_5") (pintype "bidirectional"))
    )
    (net (code "9") (name "IO_SIMO") (class "Default")
      (node (ref "U3") (pin "40") (pinfunction "40_40") (pintype "bidirectional"))
      (node (ref "U5") (pin "3") (pinfunction "DI_3") (pintype "bidirectional"))
    )
    (net (code "10") (name "IO_SOMI") (class "Default")
      (node (ref "U3") (pin "41") (pinfunction "41_41") (pintype "bidirectional"))
      (node (ref "U5") (pin "7") (pinfunction "DO_7") (pintype "bidirectional"))
    )
    (net (code "11") (name "JTAG_SENSE") (class "Default")
      (node (ref "J1") (pin "4") (pinfunction "4_4") (pintype "passive"))
      (node (ref "S3") (pin "5") (pinfunction "5_5") (pintype "bidirectional"))
    )
    (net (code "12") (name "JTAG_VCC") (class "Default")
      (node (ref "J1") (pin "2") (pinfunction "2_2") (pintype "passive"))
      (node (ref "S3") (pin "3") (pinfunction "3_3") (pintype "bidirectional"))
    )
    (net (code "13") (name "LDO") (class "Default")
      (node (ref "U1") (pin "10") (pinfunction "LDO_10") (pintype "power_in"))
    )
    (net (code "14") (name "LDO_FB") (class "Default")
      (node (ref "U1") (pin "9") (pinfunction "LDO_FB_9") (pintype "power_in"))
    )
    (net (code "15") (name "LIGHT_INT") (class "Default")
      (node (ref "R9") (pin "1") (pinfunction "1_1") (pintype "passive"))
      (node (ref "U3") (pin "58") (pinfunction "58_58") (pintype "bidirectional"))
      (node (ref "U7") (pin "5") (pinfunction "INT_5") (pintype "output"))
    )
    (net (code "16") (name "MOTION_ENABLE") (class "Default")
      (node (ref "Q4") (pin "1") (pinfunction "G_1") (pintype "passive"))
      (node (ref "U3") (pin "59") (pinfunction "59_59") (pintype "bidirectional"))
    )
    (net (code "17") (name "MOTION_INT") (class "Default")
      (node (ref "JP2") (pin "2") (pinfunction "2_2") (pintype "passive"))
      (node (ref "U3") (pin "60") (pinfunction "60_60") (pintype "bidirectional"))
    )
    (net (code "18") (name "Net-(C1-Pad1)") (class "Default")
      (node (ref "C1") (pin "1") (pinfunction "1_1") (pintype "passive"))
      (node (ref "R1") (pin "1") (pinfunction "1_1") (pintype "passive"))
      (node (ref "U3") (pin "11") (pinfunction "11_11") (pintype "power_in"))
    )
    (net (code "19") (name "Net-(C10-Pad2)") (class "Default")
      (node (ref "C10") (pin "2") (pinfunction "2_2") (pintype "passive"))
      (node (ref "U3") (pin "20") (pinfunction "20_20") (pintype "power_in"))
    )
    (net (code "20") (name "Net-(C11-P$1)") (class "Default")
      (node (ref "C11") (pin "1") (pinfunction "P$1_1") (pintype "passive"))
      (node (ref "U2") (pin "2") (pinfunction "CAP_2") (pintype "power_in"))
    )
    (net (code "21") (name "Net-(C16-Pad1)") (class "Default")
      (node (ref "C16") (pin "1") (pinfunction "1_1") (pintype "passive"))
      (node (ref "U3") (pin "67") (pinfunction "67_67") (pintype "power_in"))
    )
    (net (code "22") (name "Net-(C17-Pad1)") (class "Default")
      (node (ref "C17") (pin "1") (pinfunction "1_1") (pintype "passive"))
      (node (ref "U3") (pin "66") (pinfunction "66_66") (pintype "power_in"))
    )
    (net (code "23") (name "Net-(C23-P$1)") (class "Default")
      (node (ref "C23") (pin "1") (pinfunction "P$1_1") (pintype "passive"))
      (node (ref "U6") (pin "VDD") (pinfunction "VDD_VDD") (pintype "power_in"))
    )
    (net (code "24") (name "Net-(C25-P$2)") (class "Default")
      (node (ref "C25") (pin "2") (pinfunction "P$2_2") (pintype "passive"))
      (node (ref "D8") (pin "2") (pinfunction "2_2") (pintype "passive"))
      (node (ref "J3") (pin "1") (pinfunction "2_1") (pintype "passive"))
      (node (ref "U6") (pin "BAT") (pinfunction "BAT_BAT") (pintype "power_in"))
      (node (ref "U6") (pin "SRP") (pinfunction "SRP_SRP") (pintype "bidirectional"))
    )
    (net (code "25") (name "Net-(C29-Pad1)") (class "Default")
      (node (ref "C29") (pin "1") (pinfunction "1_1") (pintype "passive"))
      (node (ref "U8") (pin "6") (pinfunction "6_6") (pintype "power_in"))
    )
    (net (code "26") (name "Net-(C173-Pad2)") (class "Default")
      (node (ref "C173") (pin "2") (pinfunction "2_2") (pintype "passive"))
      (node (ref "L171") (pin "2") (pinfunction "2_2") (pintype "passive"))
      (node (ref "R171") (pin "1") (pinfunction "1_1") (pintype "passive"))
    )
    (net (code "27") (name "Net-(C174-Pad1)") (class "Default")
      (node (ref "C174") (pin "1") (pinfunction "1_1") (pintype "passive"))
      (node (ref "L171") (pin "1") (pinfunction "1_1") (pintype "passive"))
      (node (ref "U8") (pin "17") (pinfunction "17_17") (pintype "bidirectional"))
    )
    (net (code "28") (name "Net-(C174-Pad2)") (class "Default")
      (node (ref "C174") (pin "2") (pinfunction "2_2") (pintype "passive"))
      (node (ref "C176") (pin "1") (pinfunction "1_1") (pintype "passive"))
      (node (ref "L172") (pin "1") (pinfunction "1_1") (pintype "passive"))
    )
    (net (code "29") (name "Net-(C175-Pad1)") (class "Default")
      (node (ref "C175") (pin "1") (pinfunction "1_1") (pintype "passive"))
      (node (ref "L173") (pin "2") (pinfunction "2_2") (pintype "passive"))
      (node (ref "L174") (pin "1") (pinfunction "1_1") (pintype "passive"))
    )
    (net (code "30") (name "Net-(C176-Pad2)") (class "Default")
      (node (ref "C176") (pin "2") (pinfunction "2_2") (pintype "passive"))
      (node (ref "C181") (pin "2") (pinfunction "2_2") (pintype "passive"))
      (node (ref "L172") (pin "2") (pinfunction "2_2") (pintype "passive"))
      (node (ref "L173") (pin "1") (pinfunction "1_1") (pintype "passive"))
    )
    (net (code "31") (name "Net-(C181-Pad1)") (class "Default")
      (node (ref "C181") (pin "1") (pinfunction "1_1") (pintype "passive"))
      (node (ref "L193") (pin "2") (pinfunction "2_2") (pintype "passive"))
      (node (ref "U8") (pin "18") (pinfunction "18_18") (pintype "bidirectional"))
    )
    (net (code "32") (name "Net-(C191-Pad1)") (class "Default")
      (node (ref "C191") (pin "1") (pinfunction "1_1") (pintype "passive"))
      (node (ref "L191") (pin "1") (pinfunction "1_1") (pintype "passive"))
      (node (ref "L192") (pin "1") (pinfunction "1_1") (pintype "passive"))
      (node (ref "U8") (pin "19") (pinfunction "19_19") (pintype "bidirectional"))
    )
    (net (code "33") (name "Net-(C191-Pad2)") (class "Default")
      (node (ref "C191") (pin "2") (pinfunction "2_2") (pintype "passive"))
      (node (ref "L193") (pin "1") (pinfunction "1_1") (pintype "passive"))
      (node (ref "L201") (pin "2") (pinfunction "2_2") (pintype "passive"))
    )
    (net (code "34") (name "Net-(C201-Pad1)") (class "Default")
      (node (ref "C201") (pin "1") (pinfunction "1_1") (pintype "passive"))
      (node (ref "L191") (pin "2") (pinfunction "2_2") (pintype "passive"))
      (node (ref "L201") (pin "1") (pinfunction "1_1") (pintype "passive"))
      (node (ref "U8") (pin "20") (pinfunction "20_20") (pintype "bidirectional"))
    )
    (net (code "35") (name "Net-(C211-Pad1)") (class "Default")
      (node (ref "C211") (pin "1") (pinfunction "1_1") (pintype "passive"))
      (node (ref "U8") (pin "21") (pinfunction "21_21") (pintype "power_in"))
    )
    (net (code "36") (name "Net-(C221-Pad2)") (class "Default")
      (node (ref "C221") (pin "2") (pinfunction "2_2") (pintype "passive"))
      (node (ref "U8") (pin "22") (pinfunction "22_22") (pintype "power_in"))
    )
    (net (code "37") (name "Net-(C231-Pad1)") (class "Default")
      (node (ref "C231") (pin "1") (pinfunction "1_1") (pintype "passive"))
      (node (ref "U8") (pin "24") (pinfunction "24_24") (pintype "bidirectional"))
    )
    (net (code "38") (name "Net-(C231-Pad2)") (class "Default")
      (node (ref "C231") (pin "2") (pinfunction "2_2") (pintype "passive"))
      (node (ref "U8") (pin "23") (pinfunction "23_23") (pintype "bidirectional"))
    )
    (net (code "39") (name "Net-(CHARGE-PadC)") (class "Default")
      (node (ref "CHARGE") (pin "C") (pinfunction "C_C") (pintype "passive"))
      (node (ref "R6") (pin "1") (pinfunction "1_1") (pintype "passive"))
    )
    (net (code "40") (name "Net-(CN1-PadGND)") (class "Default")
      (node (ref "CN1") (pin "GND") (pinfunction "GND_GND") (pintype "power_in"))
      (node (ref "R2") (pin "1") (pinfunction "1_1") (pintype "passive"))
    )
    (net (code "41") (name "Net-(D9-Pad1)") (class "Default")
      (node (ref "D9") (pin "1") (pinfunction "1_1") (pintype "passive"))
      (node (ref "U6") (pin "PROG") (pinfunction "PROG_PROG") (pintype "bidirectional"))
    )
    (net (code "42") (name "Net-(D10-Pad1)") (class "Default")
      (node (ref "D10") (pin "1") (pinfunction "1_1") (pintype "passive"))
      (node (ref "U6") (pin "TEST") (pinfunction "TEST_TEST") (pintype "bidirectional"))
    )
    (net (code "43") (name "Net-(G1-PadC)") (class "Default")
      (node (ref "G1") (pin "C") (pinfunction "C_C") (pintype "passive"))
      (node (ref "R10") (pin "2") (pinfunction "2_2") (pintype "passive"))
    )
    (net (code "44") (name "Net-(G2-PadC)") (class "Default")
      (node (ref "G2") (pin "C") (pinfunction "C_C") (pintype "passive"))
      (node (ref "R24") (pin "2") (pinfunction "2_2") (pintype "passive"))
    )
    (net (code "45") (name "Net-(G3-PadC)") (class "Default")
      (node (ref "G3") (pin "C") (pinfunction "C_C") (pintype "passive"))
      (node (ref "R25") (pin "2") (pinfunction "2_2") (pintype "passive"))
    )
    (net (code "46") (name "Net-(L174-Pad2)") (class "Default")
      (node (ref "L174") (pin "2") (pinfunction "2_2") (pintype "passive"))
      (node (ref "R181") (pin "1") (pinfunction "1_1") (pintype "passive"))
    )
    (net (code "47") (name "Net-(POWER-PadC)") (class "Default")
      (node (ref "POWER") (pin "C") (pinfunction "C_C") (pintype "passive"))
      (node (ref "R27") (pin "2") (pinfunction "2_2") (pintype "passive"))
    )
    (net (code "48") (name "Net-(Q1-1)") (class "Default")
      (node (ref "Q1") (pin "P1") (pinfunction "1_P1") (pintype "bidirectional"))
      (node (ref "U3") (pin "13") (pinfunction "13_13") (pintype "bidirectional"))
    )
    (net (code "49") (name "Net-(Q1-2)") (class "Default")
      (node (ref "Q1") (pin "P2") (pinfunction "2_P2") (pintype "bidirectional"))
      (node (ref "U3") (pin "12") (pinfunction "12_12") (pintype "bidirectional"))
    )
    (net (code "50") (name "Net-(Q2-Pad1)") (class "Default")
      (node (ref "Q2") (pin "1") (pinfunction "1_1") (pintype "passive"))
      (node (ref "U3") (pin "70") (pinfunction "70_70") (pintype "bidirectional"))
    )
    (net (code "51") (name "Net-(Q2-Pad3)") (class "Default")
      (node (ref "Q2") (pin "3") (pinfunction "3_3") (pintype "passive"))
      (node (ref "U3") (pin "69") (pinfunction "69_69") (pintype "bidirectional"))
    )
    (net (code "52") (name "Net-(Q3-X1)") (class "Default")
      (node (ref "C28") (pin "1") (pinfunction "1_1") (pintype "passive"))
      (node (ref "Q3") (pin "1") (pinfunction "X1_1") (pintype "bidirectional"))
      (node (ref "U8") (pin "30") (pinfunction "30_30") (pintype "bidirectional"))
    )
    (net (code "53") (name "Net-(Q3-X2)") (class "Default")
      (node (ref "C32") (pin "1") (pinfunction "1_1") (pintype "passive"))
      (node (ref "Q3") (pin "3") (pinfunction "X2_3") (pintype "bidirectional"))
      (node (ref "U8") (pin "31") (pinfunction "31_31") (pintype "bidirectional"))
    )
    (net (code "54") (name "Net-(Q4-S)") (class "Default")
      (node (ref "JP2") (pin "3") (pinfunction "3_3") (pintype "passive"))
      (node (ref "Q4") (pin "2") (pinfunction "S_2") (pintype "passive"))
    )
    (net (code "55") (name "Net-(Q5-S)") (class "Default")
      (node (ref "Q5") (pin "2") (pinfunction "S_2") (pintype "passive"))
      (node (ref "U5") (pin "4") (pinfunction "VCC_4") (pintype "bidirectional"))
      (node (ref "U5") (pin "8") (pinfunction "RSV_8") (pintype "bidirectional"))
    )
    (net (code "56") (name "Net-(R12-Pad1)") (class "Default")
      (node (ref "R12") (pin "1") (pinfunction "1_1") (pintype "passive"))
      (node (ref "U8") (pin "14") (pinfunction "14_14") (pintype "power_in"))
    )
    (net (code "57") (name "Net-(S2-S)") (class "Default")
      (node (ref "R7") (pin "1") (pinfunction "1_1") (pintype "passive"))
      (node (ref "S2") (pin "2") (pinfunction "S_2") (pintype "passive"))
    )
    (net (code "58") (name "Net-(SMA-SIGNAL)") (class "Default")
      (node (ref "R181") (pin "2") (pinfunction "2_2") (pintype "passive"))
      (node (ref "SMA") (pin "SIG") (pinfunction "SIGNAL_SIG") (pintype "bidirectional"))
    )
    (net (code "59") (name "Net-(U1-BUCK_FB)") (class "Default")
      (node (ref "C12") (pin "2") (pinfunction "2_2") (pintype "passive"))
      (node (ref "R16") (pin "1") (pinfunction "1_1") (pintype "passive"))
      (node (ref "R17") (pin "1") (pinfunction "1_1") (pintype "passive"))
      (node (ref "U1") (pin "8") (pinfunction "BUCK_FB_8") (pintype "power_in"))
    )
    (net (code "60") (name "Net-(U1-BVIN)") (class "Default")
      (node (ref "C4") (pin "1") (pinfunction "1_1") (pintype "passive"))
      (node (ref "C5") (pin "1") (pinfunction "1_1") (pintype "passive"))
      (node (ref "CHARGE") (pin "A") (pinfunction "A_A") (pintype "passive"))
      (node (ref "POWER") (pin "A") (pinfunction "A_A") (pintype "passive"))
      (node (ref "U1") (pin "12") (pinfunction "BVIN_12") (pintype "power_in"))
      (node (ref "U1") (pin "18") (pinfunction "VOUT_18") (pintype "power_in"))
    )
    (net (code "61") (name "Net-(U1-CHRG)") (class "Default")
      (node (ref "R6") (pin "2") (pinfunction "2_2") (pintype "passive"))
      (node (ref "U1") (pin "14") (pinfunction "CHRG_14") (pintype "input"))
    )
    (net (code "62") (name "Net-(U1-PROG)") (class "Default")
      (node (ref "R26") (pin "2") (pinfunction "2_2") (pintype "passive"))
      (node (ref "U1") (pin "16") (pinfunction "PROG_16") (pintype "power_in"))
    )
    (net (code "63") (name "Net-(U1-SW)") (class "Default")
      (node (ref "L10") (pin "2") (pinfunction "2_2") (pintype "passive"))
      (node (ref "U1") (pin "13") (pinfunction "SW_13") (pintype "power_in"))
    )
    (net (code "64") (name "Net-(U11-CH1_IN)") (class "Default")
      (node (ref "CN1") (pin "D+") (pinfunction "D+_D+") (pintype "bidirectional"))
      (node (ref "U11") (pin "3") (pinfunction "CH1_IN_3") (pintype "input"))
    )
    (net (code "65") (name "Net-(U11-CH1_OUT)") (class "Default")
      (node (ref "R4") (pin "1") (pinfunction "1_1") (pintype "passive"))
      (node (ref "U11") (pin "1") (pinfunction "CH1_OUT_1") (pintype "output"))
    )
    (net (code "66") (name "Net-(U11-CH2_IN)") (class "Default")
      (node (ref "CN1") (pin "D-") (pinfunction "D-_D-") (pintype "bidirectional"))
      (node (ref "U11") (pin "4") (pinfunction "CH2_IN_4") (pintype "input"))
    )
    (net (code "67") (name "Net-(U11-CH2_OUT)") (class "Default")
      (node (ref "R5") (pin "1") (pinfunction "1_1") (pintype "passive"))
      (node (ref "U11") (pin "6") (pinfunction "CH2_OUT_6") (pintype "output"))
    )
    (net (code "68") (name "P1.0") (class "Default")
      (node (ref "J2") (pin "20") (pinfunction "20_20") (pintype "passive"))
      (node (ref "U3") (pin "21") (pinfunction "21_21") (pintype "bidirectional"))
    )
    (net (code "69") (name "P1.1") (class "Default")
      (node (ref "J2") (pin "17") (pinfunction "17_17") (pintype "passive"))
      (node (ref "U3") (pin "22") (pinfunction "22_22") (pintype "bidirectional"))
    )
    (net (code "70") (name "P1.2") (class "Default")
      (node (ref "J2") (pin "18") (pinfunction "18_18") (pintype "passive"))
      (node (ref "U3") (pin "23") (pinfunction "23_23") (pintype "bidirectional"))
    )
    (net (code "71") (name "P1.3") (class "Default")
      (node (ref "J2") (pin "15") (pinfunction "15_15") (pintype "passive"))
      (node (ref "U3") (pin "24") (pinfunction "24_24") (pintype "bidirectional"))
    )
    (net (code "72") (name "P1.4") (class "Default")
      (node (ref "J2") (pin "16") (pinfunction "16_16") (pintype "passive"))
      (node (ref "U3") (pin "25") (pinfunction "25_25") (pintype "bidirectional"))
    )
    (net (code "73") (name "P2.2") (class "Default")
      (node (ref "J2") (pin "13") (pinfunction "13_13") (pintype "passive"))
      (node (ref "U3") (pin "31") (pinfunction "31_31") (pintype "bidirectional"))
    )
    (net (code "74") (name "P2.3") (class "Default")
      (node (ref "J2") (pin "14") (pinfunction "14_14") (pintype "passive"))
      (node (ref "U3") (pin "32") (pinfunction "32_32") (pintype "bidirectional"))
    )
    (net (code "75") (name "P2.4") (class "Default")
      (node (ref "J2") (pin "11") (pinfunction "11_11") (pintype "passive"))
      (node (ref "U3") (pin "33") (pinfunction "33_33") (pintype "bidirectional"))
    )
    (net (code "76") (name "P2.5") (class "Default")
      (node (ref "J2") (pin "12") (pinfunction "12_12") (pintype "passive"))
      (node (ref "U3") (pin "34") (pinfunction "34_34") (pintype "bidirectional"))
    )
    (net (code "77") (name "P2.6") (class "Default")
      (node (ref "J2") (pin "9") (pinfunction "9_9") (pintype "passive"))
      (node (ref "U3") (pin "35") (pinfunction "35_35") (pintype "bidirectional"))
    )
    (net (code "78") (name "PRESSURE_INT") (class "Default")
      (node (ref "R23") (pin "1") (pinfunction "1_1") (pintype "passive"))
      (node (ref "U2") (pin "6") (pinfunction "INT1_6") (pintype "output"))
      (node (ref "U3") (pin "43") (pinfunction "43_43") (pintype "bidirectional"))
    )
    (net (code "79") (name "REGULATOR_BUCK_ON") (class "Default")
      (node (ref "U1") (pin "7") (pinfunction "BUCK_ON_7") (pintype "input"))
      (node (ref "U3") (pin "2") (pinfunction "2_2") (pintype "bidirectional"))
    )
    (net (code "80") (name "REGULATOR_HPWR") (class "Default")
      (node (ref "U1") (pin "1") (pinfunction "HPWR_1") (pintype "input"))
      (node (ref "U3") (pin "1") (pinfunction "1_1") (pintype "bidirectional"))
    )
    (net (code "81") (name "REGULATOR_VCC") (class "Default")
      (node (ref "C12") (pin "1") (pinfunction "1_1") (pintype "passive"))
      (node (ref "C13") (pin "1") (pinfunction "1_1") (pintype "passive"))
      (node (ref "L10") (pin "1") (pinfunction "1_1") (pintype "passive"))
      (node (ref "R16") (pin "2") (pinfunction "2_2") (pintype "passive"))
      (node (ref "S3") (pin "1") (pinfunction "1_1") (pintype "bidirectional"))
      (node (ref "S3") (pin "4") (pinfunction "4_4") (pintype "bidirectional"))
    )
    (net (code "82") (name "RF_CLK") (class "Default")
      (node (ref "U3") (pin "39") (pinfunction "39_39") (pintype "bidirectional"))
      (node (ref "U8") (pin "8") (pinfunction "8_8") (pintype "bidirectional"))
    )
    (net (code "83") (name "RF_CSN") (class "Default")
      (node (ref "U3") (pin "53") (pinfunction "53_53") (pintype "bidirectional"))
      (node (ref "U8") (pin "11") (pinfunction "11_11") (pintype "bidirectional"))
    )
    (net (code "84") (name "RF_GPIO0") (class "Default")
      (node (ref "U3") (pin "54") (pinfunction "54_54") (pintype "bidirectional"))
      (node (ref "U8") (pin "10") (pinfunction "10_10") (pintype "bidirectional"))
    )
    (net (code "85") (name "RF_GPIO2") (class "Default")
      (node (ref "U3") (pin "55") (pinfunction "55_55") (pintype "bidirectional"))
      (node (ref "U8") (pin "4") (pinfunction "4_4") (pintype "bidirectional"))
    )
    (net (code "86") (name "RF_GPIO3") (class "Default")
      (node (ref "U3") (pin "56") (pinfunction "56_56") (pintype "bidirectional"))
      (node (ref "U8") (pin "3") (pinfunction "3_3") (pintype "input"))
    )
    (net (code "87") (name "RF_LED") (class "Default")
      (node (ref "G3") (pin "A") (pinfunction "A_A") (pintype "passive"))
      (node (ref "U3") (pin "28") (pinfunction "28_28") (pintype "bidirectional"))
    )
    (net (code "88") (name "RF_RESET") (class "Default")
      (node (ref "U3") (pin "57") (pinfunction "57_57") (pintype "bidirectional"))
      (node (ref "U8") (pin "2") (pinfunction "2_2") (pintype "input"))
    )
    (net (code "89") (name "RF_SIMO") (class "Default")
      (node (ref "U3") (pin "37") (pinfunction "37_37") (pintype "bidirectional"))
      (node (ref "U8") (pin "7") (pinfunction "7_7") (pintype "bidirectional"))
    )
    (net (code "90") (name "RF_SOMI") (class "Default")
      (node (ref "U3") (pin "38") (pinfunction "38_38") (pintype "bidirectional"))
      (node (ref "U8") (pin "9") (pinfunction "9_9") (pintype "bidirectional"))
    )
    (net (code "91") (name "RST{slash}SBWTDIO") (class "Default")
      (node (ref "C8") (pin "1") (pinfunction "1_1") (pintype "passive"))
      (node (ref "J1") (pin "11") (pinfunction "11_11") (pintype "passive"))
      (node (ref "R3") (pin "1") (pinfunction "1_1") (pintype "passive"))
      (node (ref "S1") (pin "2") (pinfunction "S_2") (pintype "passive"))
      (node (ref "U3") (pin "76") (pinfunction "76_76") (pintype "bidirectional"))
    )
    (net (code "92") (name "SENSOR_LED") (class "Default")
      (node (ref "G2") (pin "A") (pinfunction "A_A") (pintype "passive"))
      (node (ref "U3") (pin "27") (pinfunction "27_27") (pintype "bidirectional"))
    )
    (net (code "93") (name "TARGET_PUR") (class "Default")
      (node (ref "R7") (pin "2") (pinfunction "2_2") (pintype "passive"))
      (node (ref "R8") (pin "2") (pinfunction "2_2") (pintype "passive"))
      (node (ref "U3") (pin "63") (pinfunction "63_63") (pintype "bidirectional"))
    )
    (net (code "94") (name "TCK") (class "Default")
      (node (ref "J1") (pin "7") (pinfunction "7_7") (pintype "passive"))
      (node (ref "U3") (pin "75") (pinfunction "75_75") (pintype "bidirectional"))
    )
    (net (code "95") (name "TDI") (class "Default")
      (node (ref "J1") (pin "3") (pinfunction "3_3") (pintype "passive"))
      (node (ref "U3") (pin "73") (pinfunction "73_73") (pintype "bidirectional"))
    )
    (net (code "96") (name "TDO") (class "Default")
      (node (ref "J1") (pin "1") (pinfunction "1_1") (pintype "passive"))
      (node (ref "U3") (pin "72") (pinfunction "72_72") (pintype "bidirectional"))
    )
    (net (code "97") (name "TEST{slash}SBWTCK") (class "Default")
      (node (ref "J1") (pin "8") (pinfunction "8_8") (pintype "passive"))
      (node (ref "U3") (pin "71") (pinfunction "71_71") (pintype "input"))
    )
    (net (code "98") (name "TMS") (class "Default")
      (node (ref "J1") (pin "5") (pinfunction "5_5") (pintype "passive"))
      (node (ref "U3") (pin "74") (pinfunction "74_74") (pintype "bidirectional"))
    )
    (net (code "99") (name "UCA1_CLK") (class "Default")
      (node (ref "J2") (pin "10") (pinfunction "10_10") (pintype "passive"))
      (node (ref "U3") (pin "45") (pinfunction "45_45") (pintype "bidirectional"))
    )
    (net (code "100") (name "UCA1_RXD") (class "Default")
      (node (ref "J2") (pin "3") (pinfunction "3_3") (pintype "passive"))
      (node (ref "U3") (pin "52") (pinfunction "52_52") (pintype "bidirectional"))
    )
    (net (code "101") (name "UCA1_STE") (class "Default")
      (node (ref "J2") (pin "8") (pinfunction "8_8") (pintype "passive"))
      (node (ref "U3") (pin "48") (pinfunction "48_48") (pintype "bidirectional"))
    )
    (net (code "102") (name "UCA1_TXD") (class "Default")
      (node (ref "J2") (pin "5") (pinfunction "5_5") (pintype "passive"))
      (node (ref "U3") (pin "51") (pinfunction "51_51") (pintype "bidirectional"))
    )
    (net (code "103") (name "USB_DM") (class "Default")
      (node (ref "C21") (pin "1") (pinfunction "P$1_1") (pintype "passive"))
      (node (ref "R5") (pin "2") (pinfunction "2_2") (pintype "passive"))
      (node (ref "U3") (pin "64") (pinfunction "64_64") (pintype "bidirectional"))
    )
    (net (code "104") (name "USB_DP") (class "Default")
      (node (ref "C18") (pin "1") (pinfunction "P$1_1") (pintype "passive"))
      (node (ref "R4") (pin "2") (pinfunction "2_2") (pintype "passive"))
      (node (ref "U3") (pin "62") (pinfunction "62_62") (pintype "bidirectional"))
    )
    (net (code "105") (name "USB_VBUS") (class "Default")
      (node (ref "C402") (pin "1") (pinfunction "1_1") (pintype "passive"))
      (node (ref "C403") (pin "+") (pinfunction "+_+") (pintype "passive"))
      (node (ref "CN1") (pin "VBUS") (pinfunction "VBUS_VBUS") (pintype "power_in"))
      (node (ref "J2") (pin "19") (pinfunction "19_19") (pintype "passive"))
      (node (ref "S2") (pin "1") (pinfunction "P_1") (pintype "passive"))
      (node (ref "U1") (pin "20") (pinfunction "VBUS_20") (pintype "power_in"))
      (node (ref "U11") (pin "5") (pinfunction "VCC_5") (pintype "power_in"))
      (node (ref "U3") (pin "65") (pinfunction "65_65") (pintype "power_in"))
    )
    (net (code "106") (name "VBAT+") (class "Default")
      (node (ref "D8") (pin "1") (pinfunction "1_1") (pintype "passive"))
      (node (ref "U1") (pin "17") (pinfunction "BAT_17") (pintype "power_in"))
      (node (ref "U6") (pin "SRN") (pinfunction "SRN_SRN") (pintype "bidirectional"))
    )
    (net (code "107") (name "VCC") (class "Default")
      (node (ref "C171") (pin "1") (pinfunction "1_1") (pintype "passive"))
      (node (ref "C172") (pin "1") (pinfunction "1_1") (pintype "passive"))
      (node (ref "C173") (pin "1") (pinfunction "1_1") (pintype "passive"))
      (node (ref "C19") (pin "1") (pinfunction "P$1_1") (pintype "passive"))
      (node (ref "C2") (pin "2") (pinfunction "2_2") (pintype "passive"))
      (node (ref "C22") (pin "+") (pinfunction "+_+") (pintype "passive"))
      (node (ref "C221") (pin "1") (pinfunction "1_1") (pintype "passive"))
      (node (ref "C24") (pin "1") (pinfunction "1_1") (pintype "passive"))
      (node (ref "C26") (pin "1") (pinfunction "1_1") (pintype "passive"))
      (node (ref "C27") (pin "1") (pinfunction "1_1") (pintype "passive"))
      (node (ref "C3") (pin "+") (pinfunction "+_+") (pintype "passive"))
      (node (ref "C30") (pin "1") (pinfunction "1_1") (pintype "passive"))
      (node (ref "C31") (pin "1") (pinfunction "P$1_1") (pintype "passive"))
      (node (ref "C33") (pin "1") (pinfunction "1_1") (pintype "passive"))
      (node (ref "C34") (pin "1") (pinfunction "1_1") (pintype "passive"))
      (node (ref "C38") (pin "1") (pinfunction "1_1") (pintype "passive"))
      (node (ref "C40") (pin "1") (pinfunction "1_1") (pintype "passive"))
      (node (ref "C42") (pin "1") (pinfunction "1_1") (pintype "passive"))
      (node (ref "C45") (pin "1") (pinfunction "1_1") (pintype "passive"))
      (node (ref "C48") (pin "1") (pinfunction "1_1") (pintype "passive"))
      (node (ref "C6") (pin "2") (pinfunction "2_2") (pintype "passive"))
      (node (ref "C7") (pin "1") (pinfunction "P$1_1") (pintype "passive"))
      (node (ref "C9") (pin "1") (pinfunction "P$1_1") (pintype "passive"))
      (node (ref "J2") (pin "1") (pinfunction "1_1") (pintype "passive"))
      (node (ref "Q4") (pin "3") (pinfunction "D_3") (pintype "passive"))
      (node (ref "Q5") (pin "3") (pinfunction "D_3") (pintype "passive"))
      (node (ref "R1") (pin "2") (pinfunction "2_2") (pintype "passive"))
      (node (ref "R171") (pin "2") (pinfunction "2_2") (pintype "passive"))
      (node (ref "R18") (pin "2") (pinfunction "2_2") (pintype "passive"))
      (node (ref "R19") (pin "2") (pinfunction "2_2") (pintype "passive"))
      (node (ref "R20") (pin "2") (pinfunction "2_2") (pintype "passive"))
      (node (ref "R21") (pin "2") (pinfunction "2_2") (pintype "passive"))
      (node (ref "R23") (pin "2") (pinfunction "2_2") (pintype "passive"))
      (node (ref "R3") (pin "2") (pinfunction "2_2") (pintype "passive"))
      (node (ref "R9") (pin "2") (pinfunction "2_2") (pintype "passive"))
      (node (ref "S3") (pin "2") (pinfunction "2_2") (pintype "bidirectional"))
      (node (ref "U2") (pin "1") (pinfunction "VDD_1") (pintype "power_in"))
      (node (ref "U2") (pin "4") (pinfunction "VDDIO_4") (pintype "power_in"))
      (node (ref "U3") (pin "18") (pinfunction "18_18") (pintype "power_in"))
      (node (ref "U3") (pin "50") (pinfunction "50_50") (pintype "power_in"))
      (node (ref "U4") (pin "VDD") (pinfunction "VDD_VDD") (pintype "power_in"))
      (node (ref "U7") (pin "1") (pinfunction "VDD_1") (pintype "power_in"))
      (node (ref "U8") (pin "1") (pinfunction "1_1") (pintype "power_in"))
      (node (ref "U8") (pin "12") (pinfunction "12_12") (pintype "power_in"))
      (node (ref "U8") (pin "13") (pinfunction "13_13") (pintype "power_in"))
      (node (ref "U8") (pin "15") (pinfunction "15_15") (pintype "power_in"))
      (node (ref "U8") (pin "25") (pinfunction "25_25") (pintype "power_in"))
      (node (ref "U8") (pin "26") (pinfunction "26_26") (pintype "power_in"))
      (node (ref "U8") (pin "27") (pinfunction "27_27") (pintype "power_in"))
      (node (ref "U8") (pin "28") (pinfunction "28_28") (pintype "power_in"))
      (node (ref "U8") (pin "29") (pinfunction "29_29") (pintype "input"))
      (node (ref "U8") (pin "5") (pinfunction "5_5") (pintype "power_in"))
    )
    (net (code "108") (name "VINLDO") (class "Default")
      (node (ref "U1") (pin "11") (pinfunction "VINLDO_11") (pintype "power_in"))
    )
    (net (code "109") (name "unconnected-(CN1-PadID)") (class "Default")
      (node (ref "CN1") (pin "ID") (pinfunction "ID_ID") (pintype "bidirectional"))
    )
    (net (code "110") (name "unconnected-(J1-Pad6)") (class "Default")
      (node (ref "J1") (pin "6") (pinfunction "6_6") (pintype "passive"))
    )
    (net (code "111") (name "unconnected-(J1-Pad10)") (class "Default")
      (node (ref "J1") (pin "10") (pinfunction "10_10") (pintype "passive"))
    )
    (net (code "112") (name "unconnected-(J1-Pad12)") (class "Default")
      (node (ref "J1") (pin "12") (pinfunction "12_12") (pintype "passive"))
    )
    (net (code "113") (name "unconnected-(J1-Pad13)") (class "Default")
      (node (ref "J1") (pin "13") (pinfunction "13_13") (pintype "passive"))
    )
    (net (code "114") (name "unconnected-(J1-Pad14)") (class "Default")
      (node (ref "J1") (pin "14") (pinfunction "14_14") (pintype "passive"))
    )
    (net (code "115") (name "unconnected-(J2-Pad7)") (class "Default")
      (node (ref "J2") (pin "7") (pinfunction "7_7") (pintype "passive"))
    )
    (net (code "116") (name "unconnected-(S3-Pad6)") (class "Default")
      (node (ref "S3") (pin "6") (pinfunction "6_6") (pintype "bidirectional"))
    )
    (net (code "117") (name "unconnected-(U1-ON-Pad4)") (class "Default")
      (node (ref "U1") (pin "4") (pinfunction "ON_4") (pintype "input"))
    )
    (net (code "118") (name "unconnected-(U1-PBSTAT-Pad3)") (class "Default")
      (node (ref "U1") (pin "3") (pinfunction "PBSTAT_3") (pintype "output"))
    )
    (net (code "119") (name "unconnected-(U2-INT2-Pad5)") (class "Default")
      (node (ref "U2") (pin "5") (pinfunction "INT2_5") (pintype "output"))
    )
    (net (code "120") (name "unconnected-(U3-Pad3)") (class "Default")
      (node (ref "U3") (pin "3") (pinfunction "3_3") (pintype "bidirectional"))
    )
    (net (code "121") (name "unconnected-(U3-Pad4)") (class "Default")
      (node (ref "U3") (pin "4") (pinfunction "4_4") (pintype "bidirectional"))
    )
    (net (code "122") (name "unconnected-(U3-Pad5)") (class "Default")
      (node (ref "U3") (pin "5") (pinfunction "5_5") (pintype "bidirectional"))
    )
    (net (code "123") (name "unconnected-(U3-Pad6)") (class "Default")
      (node (ref "U3") (pin "6") (pinfunction "6_6") (pintype "bidirectional"))
    )
    (net (code "124") (name "unconnected-(U3-Pad7)") (class "Default")
      (node (ref "U3") (pin "7") (pinfunction "7_7") (pintype "bidirectional"))
    )
    (net (code "125") (name "unconnected-(U3-Pad8)") (class "Default")
      (node (ref "U3") (pin "8") (pinfunction "8_8") (pintype "bidirectional"))
    )
    (net (code "126") (name "unconnected-(U3-Pad9)") (class "Default")
      (node (ref "U3") (pin "9") (pinfunction "9_9") (pintype "bidirectional"))
    )
    (net (code "127") (name "unconnected-(U3-Pad10)") (class "Default")
      (node (ref "U3") (pin "10") (pinfunction "10_10") (pintype "bidirectional"))
    )
    (net (code "128") (name "unconnected-(U3-Pad15)") (class "Default")
      (node (ref "U3") (pin "15") (pinfunction "15_15") (pintype "bidirectional"))
    )
    (net (code "129") (name "unconnected-(U3-Pad16)") (class "Default")
      (node (ref "U3") (pin "16") (pinfunction "16_16") (pintype "bidirectional"))
    )
    (net (code "130") (name "unconnected-(U3-Pad42)") (class "Default")
      (node (ref "U3") (pin "42") (pinfunction "42_42") (pintype "bidirectional"))
    )
    (net (code "131") (name "unconnected-(U3-Pad44)") (class "Default")
      (node (ref "U3") (pin "44") (pinfunction "44_44") (pintype "bidirectional"))
    )
    (net (code "132") (name "unconnected-(U3-Pad77)") (class "Default")
      (node (ref "U3") (pin "77") (pinfunction "77_77") (pintype "bidirectional"))
    )
    (net (code "133") (name "unconnected-(U3-Pad78)") (class "Default")
      (node (ref "U3") (pin "78") (pinfunction "78_78") (pintype "bidirectional"))
    )
    (net (code "134") (name "unconnected-(U3-Pad79)") (class "Default")
      (node (ref "U3") (pin "79") (pinfunction "79_79") (pintype "bidirectional"))
    )
    (net (code "135") (name "unconnected-(U3-Pad80)") (class "Default")
      (node (ref "U3") (pin "80") (pinfunction "80_80") (pintype "bidirectional"))
    )
    (net (code "136") (name "unconnected-(U5-NC-Pad1)") (class "Default")
      (node (ref "U5") (pin "1") (pinfunction "NC_1") (pintype "bidirectional"))
    )
    (net (code "137") (name "unconnected-(U5-SHIELD-PadCD2)") (class "Default")
      (node (ref "U5") (pin "CD2") (pinfunction "SHIELD_CD2") (pintype "bidirectional"))
    )
    (net (code "138") (name "unconnected-(U6-NC2-PadNC3)") (class "Default")
      (node (ref "U6") (pin "NC3") (pinfunction "NC2_NC3") (pintype "no_connect"))
    )
    (net (code "139") (name "unconnected-(U6-NC3-PadNC2)") (class "Default")
      (node (ref "U6") (pin "NC2") (pinfunction "NC3_NC2") (pintype "no_connect"))
    )
    (net (code "140") (name "unconnected-(U6-PadNC1)") (class "Default")
      (node (ref "U6") (pin "NC1") (pinfunction "NC1_NC1") (pintype "no_connect"))
    )
    (net (code "141") (name "unconnected-(U8-Pad16)") (class "Default")
      (node (ref "U8") (pin "16") (pinfunction "16_16") (pintype "no_connect"))
    )
    (net (code "142") (name "unconnected-(U8-Pad32)") (class "Default")
      (node (ref "U8") (pin "32") (pinfunction "32_32") (pintype "bidirectional"))
    )
  )
)
